# voting_machine.net
KiCad netlist of a schematic drawn in Altium Designer
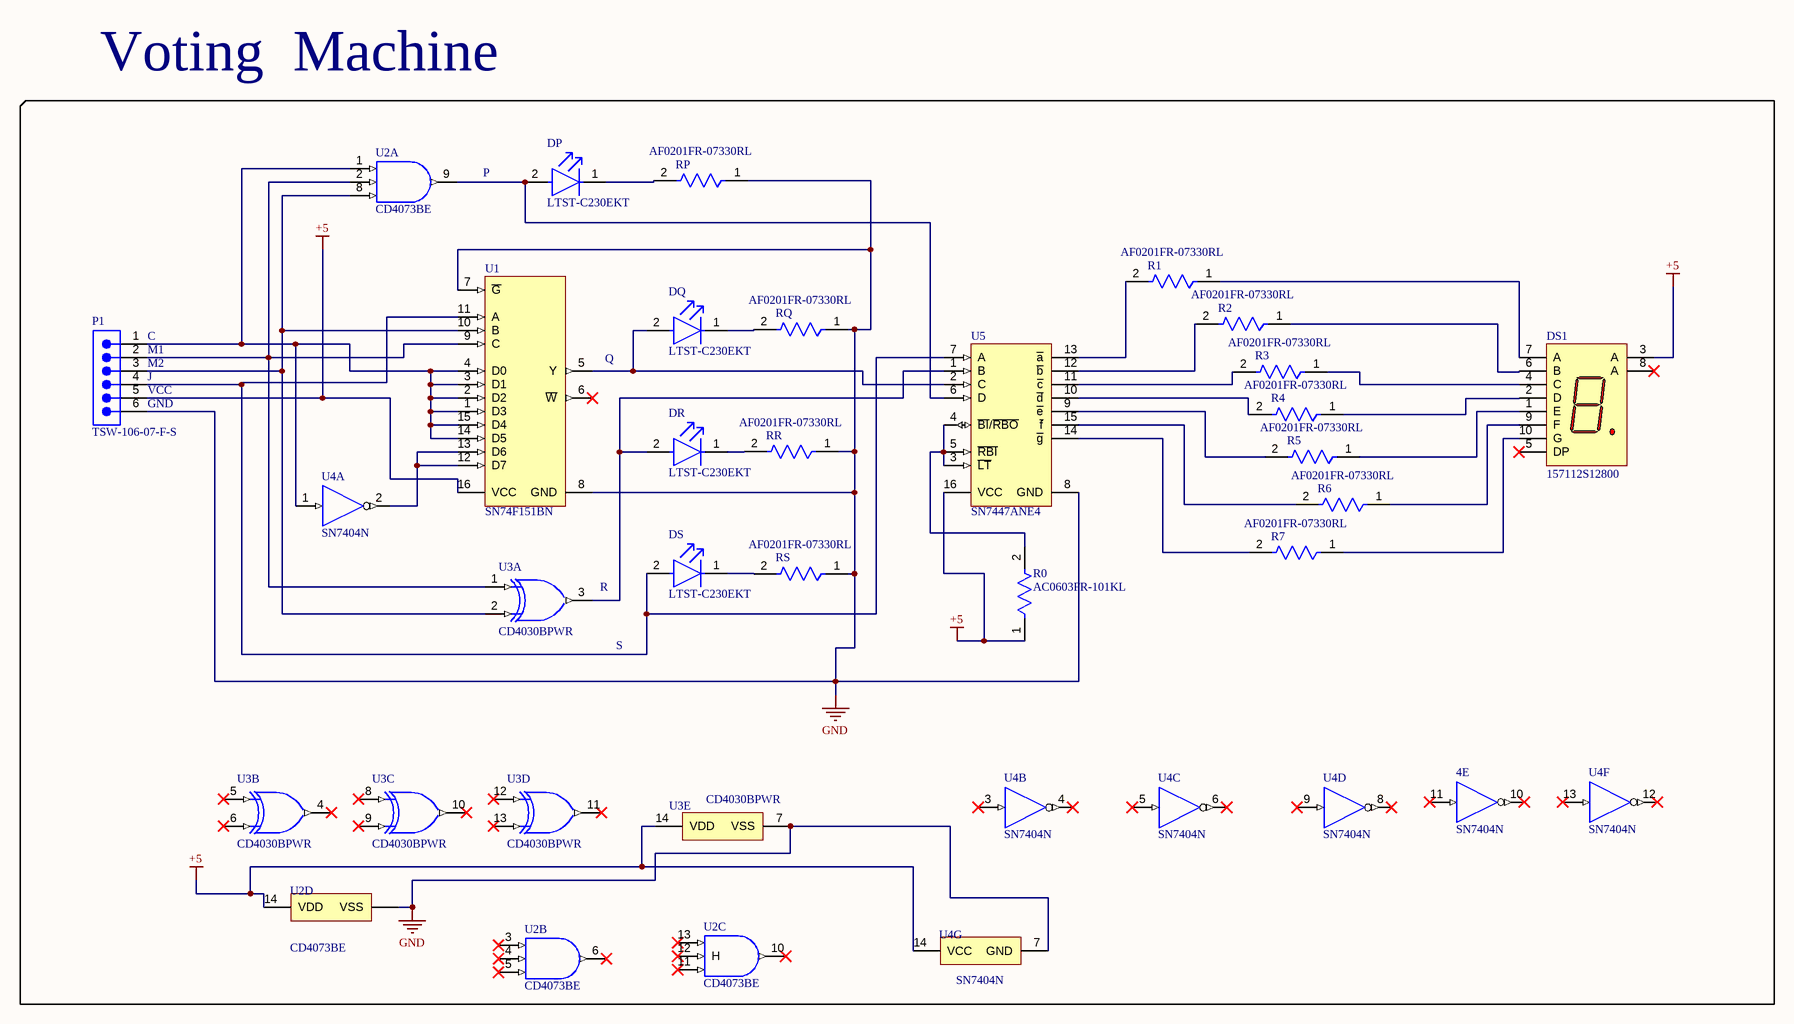
[diagram p0: voting machine.SchDoc]

(export (version "E")
  (design (tool "Eeschema 10.0.6"))
  (components
    (comp (ref "4")
      (value "SN7404N")
      (footprint "N0014A")
      (description "Hex inverters, N0014A, TUBE")
      (fields (field (name "GENERIC PART NUMBER") "SN7404") (field (name "MANUFACTURER") "Texas Instruments"))
      (libsource (lib "Altium Content Vault") (part "TI-CD_SNX4XXXXXX4X_19A-14"))
    )
    (comp (ref "DP")
      (value "LTST-C230EKT")
      (footprint "FP-LTST-C230EKT-MFG")
      (description "LED RED CLEAR CHIP SMD")
      (libsource (lib "Altium Content Vault") (part "8706943c75ba83719d021d2fdc84c58"))
    )
    (comp (ref "DQ")
      (value "LTST-C230EKT")
      (footprint "FP-LTST-C230EKT-MFG")
      (description "LED RED CLEAR CHIP SMD")
      (libsource (lib "Altium Content Vault") (part "8706943c75ba83719d021d2fdc84c58"))
    )
    (comp (ref "DR")
      (value "LTST-C230EKT")
      (footprint "FP-LTST-C230EKT-MFG")
      (description "LED RED CLEAR CHIP SMD")
      (libsource (lib "Altium Content Vault") (part "8706943c75ba83719d021d2fdc84c58"))
    )
    (comp (ref "DS")
      (value "LTST-C230EKT")
      (footprint "FP-LTST-C230EKT-MFG")
      (description "LED RED CLEAR CHIP SMD")
      (libsource (lib "Altium Content Vault") (part "8706943c75ba83719d021d2fdc84c58"))
    )
    (comp (ref "DS1")
      (value "157112S12800")
      (footprint "WL-S7DS_L12W7.3H3.75")
      (description "7-Seg Display, Comm Anode, Super Red Rohs Compliant: Yes")
      (libsource (lib "Altium Content Vault") (part "7 Segments_Red_CA_type 1"))
    )
    (comp (ref "P1")
      (value "TSW-106-07-F-S")
      (footprint "SMTC-TSW-106-07-X-S")
      (description "0.025\" SQ Post Header, Through-hole, Vertical, -55 to 125 degC, 2.54 mm Pitch, 6-Pin, Male, RoHS")
      (fields (field (name "MANUFACTURER") "Samtec"))
      (libsource (lib "Altium Content Vault") (part "SMTC-TSW-106-X-X-S-X"))
    )
    (comp (ref "R0")
      (value "AC0603FR-101KL")
      (footprint "FP-AC0603-IPC_C")
      (description "RES 1kΩ 1.00% 0.1W 0603")
      (fields (field (name "TOLERANCE") "1%"))
      (libsource (lib "Altium Content Vault") (part "1029c3af85768c4190bb7ad29bc67b5"))
    )
    (comp (ref "R1")
      (value "AF0201FR-07330RL")
      (footprint "FP-AF0201-MFG")
      (description "Anti-Sulfurated Chip Resistors Automotive Grade 330Ω 1% 200ppm/°C 0201")
      (fields (field (name "TOLERANCE") "1%"))
      (libsource (lib "Altium Content Vault") (part "1029c3af85768c4190bb7ad29bc67b5"))
    )
    (comp (ref "R2")
      (value "AF0201FR-07330RL")
      (footprint "FP-AF0201-MFG")
      (description "Anti-Sulfurated Chip Resistors Automotive Grade 330Ω 1% 200ppm/°C 0201")
      (fields (field (name "TOLERANCE") "1%"))
      (libsource (lib "Altium Content Vault") (part "1029c3af85768c4190bb7ad29bc67b5"))
    )
    (comp (ref "R3")
      (value "AF0201FR-07330RL")
      (footprint "FP-AF0201-MFG")
      (description "Anti-Sulfurated Chip Resistors Automotive Grade 330Ω 1% 200ppm/°C 0201")
      (fields (field (name "TOLERANCE") "1%"))
      (libsource (lib "Altium Content Vault") (part "1029c3af85768c4190bb7ad29bc67b5"))
    )
    (comp (ref "R4")
      (value "AF0201FR-07330RL")
      (footprint "FP-AF0201-MFG")
      (description "Anti-Sulfurated Chip Resistors Automotive Grade 330Ω 1% 200ppm/°C 0201")
      (fields (field (name "TOLERANCE") "1%"))
      (libsource (lib "Altium Content Vault") (part "1029c3af85768c4190bb7ad29bc67b5"))
    )
    (comp (ref "R5")
      (value "AF0201FR-07330RL")
      (footprint "FP-AF0201-MFG")
      (description "Anti-Sulfurated Chip Resistors Automotive Grade 330Ω 1% 200ppm/°C 0201")
      (fields (field (name "TOLERANCE") "1%"))
      (libsource (lib "Altium Content Vault") (part "1029c3af85768c4190bb7ad29bc67b5"))
    )
    (comp (ref "R6")
      (value "AF0201FR-07330RL")
      (footprint "FP-AF0201-MFG")
      (description "Anti-Sulfurated Chip Resistors Automotive Grade 330Ω 1% 200ppm/°C 0201")
      (fields (field (name "TOLERANCE") "1%"))
      (libsource (lib "Altium Content Vault") (part "1029c3af85768c4190bb7ad29bc67b5"))
    )
    (comp (ref "R7")
      (value "AF0201FR-07330RL")
      (footprint "FP-AF0201-MFG")
      (description "Anti-Sulfurated Chip Resistors Automotive Grade 330Ω 1% 200ppm/°C 0201")
      (fields (field (name "TOLERANCE") "1%"))
      (libsource (lib "Altium Content Vault") (part "1029c3af85768c4190bb7ad29bc67b5"))
    )
    (comp (ref "RP")
      (value "AF0201FR-07330RL")
      (footprint "FP-AF0201-MFG")
      (description "Anti-Sulfurated Chip Resistors Automotive Grade 330Ω 1% 200ppm/°C 0201")
      (fields (field (name "TOLERANCE") "1%"))
      (libsource (lib "Altium Content Vault") (part "1029c3af85768c4190bb7ad29bc67b5"))
    )
    (comp (ref "RQ")
      (value "AF0201FR-07330RL")
      (footprint "FP-AF0201-MFG")
      (description "Anti-Sulfurated Chip Resistors Automotive Grade 330Ω 1% 200ppm/°C 0201")
      (fields (field (name "TOLERANCE") "1%"))
      (libsource (lib "Altium Content Vault") (part "1029c3af85768c4190bb7ad29bc67b5"))
    )
    (comp (ref "RR")
      (value "AF0201FR-07330RL")
      (footprint "FP-AF0201-MFG")
      (description "Anti-Sulfurated Chip Resistors Automotive Grade 330Ω 1% 200ppm/°C 0201")
      (fields (field (name "TOLERANCE") "1%"))
      (libsource (lib "Altium Content Vault") (part "1029c3af85768c4190bb7ad29bc67b5"))
    )
    (comp (ref "RS")
      (value "AF0201FR-07330RL")
      (footprint "FP-AF0201-MFG")
      (description "Anti-Sulfurated Chip Resistors Automotive Grade 330Ω 1% 200ppm/°C 0201")
      (fields (field (name "TOLERANCE") "1%"))
      (libsource (lib "Altium Content Vault") (part "1029c3af85768c4190bb7ad29bc67b5"))
    )
    (comp (ref "U1")
      (value "SN74F151BN")
      (footprint "N0016A")
      (description "8-Line To 1-Line Data Selector/Multiplexer, N0016A, TUBE")
      (fields
        (field (name "MANUFACTURER") "Texas Instruments")
        (field (name "GENERIC PART NUMBER") "SN74F151B")
      )
      (libsource (lib "Altium Content Vault") (part "TI-SNX4XXX151-16"))
    )
    (comp (ref "U2")
      (value "CD4073BE")
      (footprint "N0014A")
      (description "CMOS Triple 3-Input AND Gate, N0014A, TUBE")
      (fields
        (field (name "MANUFACTURER") "Texas Instruments")
        (field (name "GENERIC PART NUMBER") "CD4073B")
      )
      (libsource (lib "Altium Content Vault") (part "TI-CD4073B-14"))
    )
    (comp (ref "U3")
      (value "CD4030BPWR")
      (footprint "PW0014A_M")
      (description "CMOS Quad Exclusive-OR Gate, PW0014A, LARGE T&R")
      (fields
        (field (name "MANUFACTURER") "Texas Instruments")
        (field (name "GENERIC PART NUMBER") "CD4030B")
      )
      (libsource (lib "Altium Content Vault") (part "TI-XOR-4-2IN-14_A"))
    )
    (comp (ref "U4")
      (value "SN7404N")
      (footprint "N0014A")
      (description "Hex inverters, N0014A, TUBE")
      (fields (field (name "GENERIC PART NUMBER") "SN7404") (field (name "MANUFACTURER") "Texas Instruments"))
      (libsource (lib "Altium Content Vault") (part "TI-CD_SNX4XXXXXX4X_19A-14"))
    )
    (comp (ref "U5")
      (value "SN7447ANE4")
      (footprint "TI-N16")
      (description "BCD-to-7-Segment Decoder / Driver, 4.75 to 5.25 V, 0 to 70 degC, 16-pin DIP (N16), Pb-Free (RoHS)")
      (fields (field (name "MANUFACTURER") "Texas Instruments"))
      (libsource (lib "Altium Content Vault") (part "TI-SNX4XX247-16"))
    )
  )
  (nets
    (net (code "1") (name "+5") (class "Default")
      (node (ref "DS1") (pin "3") (pinfunction "A_3") (pintype "passive"))
      (node (ref "P1") (pin "5") (pinfunction "5_5") (pintype "passive"))
      (node (ref "R0") (pin "1") (pinfunction "1_1") (pintype "passive"))
      (node (ref "U1") (pin "16") (pinfunction "VCC_16") (pintype "power_in"))
      (node (ref "U2") (pin "14") (pinfunction "VDD_14") (pintype "power_in"))
      (node (ref "U3") (pin "14") (pinfunction "VDD_14") (pintype "power_in"))
      (node (ref "U4") (pin "14") (pinfunction "VCC_14") (pintype "power_in"))
      (node (ref "U5") (pin "16") (pinfunction "VCC_16") (pintype "power_in"))
    )
    (net (code "2") (name "GND") (class "Default")
      (node (ref "P1") (pin "6") (pinfunction "6_6") (pintype "passive"))
      (node (ref "RP") (pin "1") (pinfunction "1_1") (pintype "passive"))
      (node (ref "RQ") (pin "1") (pinfunction "1_1") (pintype "passive"))
      (node (ref "RR") (pin "1") (pinfunction "1_1") (pintype "passive"))
      (node (ref "RS") (pin "1") (pinfunction "1_1") (pintype "passive"))
      (node (ref "U1") (pin "7") (pinfunction "~{G}_7") (pintype "input"))
      (node (ref "U1") (pin "8") (pinfunction "GND_8") (pintype "power_in"))
      (node (ref "U2") (pin "7") (pinfunction "VSS_7") (pintype "power_in"))
      (node (ref "U3") (pin "7") (pinfunction "VSS_7") (pintype "power_in"))
      (node (ref "U4") (pin "7") (pinfunction "GND_7") (pintype "power_in"))
      (node (ref "U5") (pin "8") (pinfunction "GND_8") (pintype "power_in"))
    )
    (net (code "3") (name "Net-(DP-A)") (class "Default")
      (node (ref "DP") (pin "2") (pinfunction "A_2") (pintype "passive"))
      (node (ref "U2") (pin "9") (pinfunction "J_9") (pintype "output"))
      (node (ref "U5") (pin "6") (pinfunction "D_6") (pintype "input"))
    )
    (net (code "4") (name "Net-(DP-C)") (class "Default")
      (node (ref "DP") (pin "1") (pinfunction "C_1") (pintype "passive"))
      (node (ref "RP") (pin "2") (pinfunction "2_2") (pintype "passive"))
    )
    (net (code "5") (name "Net-(DQ-A)") (class "Default")
      (node (ref "DQ") (pin "2") (pinfunction "A_2") (pintype "passive"))
      (node (ref "U1") (pin "5") (pinfunction "Y_5") (pintype "output"))
      (node (ref "U5") (pin "2") (pinfunction "C_2") (pintype "input"))
    )
    (net (code "6") (name "Net-(DQ-C)") (class "Default")
      (node (ref "DQ") (pin "1") (pinfunction "C_1") (pintype "passive"))
      (node (ref "RQ") (pin "2") (pinfunction "2_2") (pintype "passive"))
    )
    (net (code "7") (name "Net-(DR-A)") (class "Default")
      (node (ref "DR") (pin "2") (pinfunction "A_2") (pintype "passive"))
      (node (ref "U3") (pin "3") (pinfunction "J_3") (pintype "output"))
      (node (ref "U5") (pin "1") (pinfunction "B_1") (pintype "input"))
    )
    (net (code "8") (name "Net-(DR-C)") (class "Default")
      (node (ref "DR") (pin "1") (pinfunction "C_1") (pintype "passive"))
      (node (ref "RR") (pin "2") (pinfunction "2_2") (pintype "passive"))
    )
    (net (code "9") (name "Net-(DS-A)") (class "Default")
      (node (ref "DS") (pin "2") (pinfunction "A_2") (pintype "passive"))
      (node (ref "P1") (pin "4") (pinfunction "4_4") (pintype "passive"))
      (node (ref "U1") (pin "11") (pinfunction "A_11") (pintype "input"))
      (node (ref "U5") (pin "7") (pinfunction "A_7") (pintype "input"))
    )
    (net (code "10") (name "Net-(DS-C)") (class "Default")
      (node (ref "DS") (pin "1") (pinfunction "C_1") (pintype "passive"))
      (node (ref "RS") (pin "2") (pinfunction "2_2") (pintype "passive"))
    )
    (net (code "11") (name "Net-(DS1-A-Pad7)") (class "Default")
      (node (ref "DS1") (pin "7") (pinfunction "A_7") (pintype "passive"))
      (node (ref "R1") (pin "1") (pinfunction "1_1") (pintype "passive"))
    )
    (net (code "12") (name "Net-(DS1-B)") (class "Default")
      (node (ref "DS1") (pin "6") (pinfunction "B_6") (pintype "passive"))
      (node (ref "R2") (pin "1") (pinfunction "1_1") (pintype "passive"))
    )
    (net (code "13") (name "Net-(DS1-C)") (class "Default")
      (node (ref "DS1") (pin "4") (pinfunction "C_4") (pintype "passive"))
      (node (ref "R3") (pin "1") (pinfunction "1_1") (pintype "passive"))
    )
    (net (code "14") (name "Net-(DS1-D)") (class "Default")
      (node (ref "DS1") (pin "2") (pinfunction "D_2") (pintype "passive"))
      (node (ref "R4") (pin "1") (pinfunction "1_1") (pintype "passive"))
    )
    (net (code "15") (name "Net-(DS1-E)") (class "Default")
      (node (ref "DS1") (pin "1") (pinfunction "E_1") (pintype "passive"))
      (node (ref "R5") (pin "1") (pinfunction "1_1") (pintype "passive"))
    )
    (net (code "16") (name "Net-(DS1-F)") (class "Default")
      (node (ref "DS1") (pin "9") (pinfunction "F_9") (pintype "passive"))
      (node (ref "R6") (pin "1") (pinfunction "1_1") (pintype "passive"))
    )
    (net (code "17") (name "Net-(DS1-G)") (class "Default")
      (node (ref "DS1") (pin "10") (pinfunction "G_10") (pintype "passive"))
      (node (ref "R7") (pin "1") (pinfunction "1_1") (pintype "passive"))
    )
    (net (code "18") (name "Net-(U1-B)") (class "Default")
      (node (ref "P1") (pin "3") (pinfunction "3_3") (pintype "passive"))
      (node (ref "U1") (pin "10") (pinfunction "B_10") (pintype "input"))
      (node (ref "U2") (pin "8") (pinfunction "C_8") (pintype "input"))
      (node (ref "U3") (pin "2") (pinfunction "B_2") (pintype "input"))
    )
    (net (code "19") (name "Net-(U1-C)") (class "Default")
      (node (ref "P1") (pin "2") (pinfunction "2_2") (pintype "passive"))
      (node (ref "U1") (pin "9") (pinfunction "C_9") (pintype "input"))
      (node (ref "U2") (pin "2") (pinfunction "B_2") (pintype "input"))
      (node (ref "U3") (pin "1") (pinfunction "A_1") (pintype "input"))
    )
    (net (code "20") (name "Net-(U1-D0)") (class "Default")
      (node (ref "P1") (pin "1") (pinfunction "1_1") (pintype "passive"))
      (node (ref "U1") (pin "1") (pinfunction "D3_1") (pintype "input"))
      (node (ref "U1") (pin "14") (pinfunction "D5_14") (pintype "input"))
      (node (ref "U1") (pin "15") (pinfunction "D4_15") (pintype "input"))
      (node (ref "U1") (pin "2") (pinfunction "D2_2") (pintype "input"))
      (node (ref "U1") (pin "3") (pinfunction "D1_3") (pintype "input"))
      (node (ref "U1") (pin "4") (pinfunction "D0_4") (pintype "input"))
      (node (ref "U2") (pin "1") (pinfunction "A_1") (pintype "input"))
      (node (ref "U4") (pin "1") (pinfunction "1A_1") (pintype "input"))
    )
    (net (code "21") (name "Net-(U1-D6)") (class "Default")
      (node (ref "U1") (pin "12") (pinfunction "D7_12") (pintype "input"))
      (node (ref "U1") (pin "13") (pinfunction "D6_13") (pintype "input"))
      (node (ref "U4") (pin "2") (pinfunction "~{1Y}_2") (pintype "output"))
    )
    (net (code "22") (name "Net-(U5-~{BI}{slash}~{RBO})") (class "Default")
      (node (ref "R0") (pin "2") (pinfunction "2_2") (pintype "passive"))
      (node (ref "U5") (pin "3") (pinfunction "~{LT}_3") (pintype "input"))
      (node (ref "U5") (pin "4") (pinfunction "~{BI}/~{RBO}_4") (pintype "bidirectional"))
      (node (ref "U5") (pin "5") (pinfunction "~{RBI}_5") (pintype "input"))
    )
    (net (code "23") (name "Net-(U5-~{a})") (class "Default")
      (node (ref "R1") (pin "2") (pinfunction "2_2") (pintype "passive"))
      (node (ref "U5") (pin "13") (pinfunction "~{a}_13") (pintype "open_collector"))
    )
    (net (code "24") (name "Net-(U5-~{b})") (class "Default")
      (node (ref "R2") (pin "2") (pinfunction "2_2") (pintype "passive"))
      (node (ref "U5") (pin "12") (pinfunction "~{b}_12") (pintype "open_collector"))
    )
    (net (code "25") (name "Net-(U5-~{c})") (class "Default")
      (node (ref "R3") (pin "2") (pinfunction "2_2") (pintype "passive"))
      (node (ref "U5") (pin "11") (pinfunction "~{c}_11") (pintype "open_collector"))
    )
    (net (code "26") (name "Net-(U5-~{d})") (class "Default")
      (node (ref "R4") (pin "2") (pinfunction "2_2") (pintype "passive"))
      (node (ref "U5") (pin "10") (pinfunction "~{d}_10") (pintype "open_collector"))
    )
    (net (code "27") (name "Net-(U5-~{e})") (class "Default")
      (node (ref "R5") (pin "2") (pinfunction "2_2") (pintype "passive"))
      (node (ref "U5") (pin "9") (pinfunction "~{e}_9") (pintype "open_collector"))
    )
    (net (code "28") (name "Net-(U5-~{f})") (class "Default")
      (node (ref "R6") (pin "2") (pinfunction "2_2") (pintype "passive"))
      (node (ref "U5") (pin "15") (pinfunction "~{f}_15") (pintype "open_collector"))
    )
    (net (code "29") (name "Net-(U5-~{g})") (class "Default")
      (node (ref "R7") (pin "2") (pinfunction "2_2") (pintype "passive"))
      (node (ref "U5") (pin "14") (pinfunction "~{g}_14") (pintype "open_collector"))
    )
    (net (code "30") (name "unconnected-(4E-5A-Pad11)") (class "Default")
      (node (ref "4") (pin "11") (pinfunction "5A_11") (pintype "input+no_connect"))
    )
    (net (code "31") (name "unconnected-(4E-~{5Y}-Pad10)") (class "Default")
      (node (ref "4") (pin "10") (pinfunction "~{5Y}_10") (pintype "output+no_connect"))
    )
    (net (code "32") (name "unconnected-(DS1-A-Pad8)") (class "Default")
      (node (ref "DS1") (pin "8") (pinfunction "A_8") (pintype "passive+no_connect"))
    )
    (net (code "33") (name "unconnected-(DS1-DP-Pad5)") (class "Default")
      (node (ref "DS1") (pin "5") (pinfunction "DP_5") (pintype "passive+no_connect"))
    )
    (net (code "34") (name "unconnected-(U1-~{W}-Pad6)") (class "Default")
      (node (ref "U1") (pin "6") (pinfunction "~{W}_6") (pintype "output+no_connect"))
    )
    (net (code "35") (name "unconnected-(U2B-D-Pad3)") (class "Default")
      (node (ref "U2") (pin "3") (pinfunction "D_3") (pintype "input+no_connect"))
    )
    (net (code "36") (name "unconnected-(U2B-E-Pad4)") (class "Default")
      (node (ref "U2") (pin "4") (pinfunction "E_4") (pintype "input+no_connect"))
    )
    (net (code "37") (name "unconnected-(U2B-F-Pad5)") (class "Default")
      (node (ref "U2") (pin "5") (pinfunction "F_5") (pintype "input+no_connect"))
    )
    (net (code "38") (name "unconnected-(U2B-K-Pad6)") (class "Default")
      (node (ref "U2") (pin "6") (pinfunction "K_6") (pintype "output+no_connect"))
    )
    (net (code "39") (name "unconnected-(U2C-G-Pad13)") (class "Default")
      (node (ref "U2") (pin "13") (pinfunction "G_13") (pintype "input+no_connect"))
    )
    (net (code "40") (name "unconnected-(U2C-H-Pad12)") (class "Default")
      (node (ref "U2") (pin "12") (pinfunction "H_12") (pintype "input+no_connect"))
    )
    (net (code "41") (name "unconnected-(U2C-I-Pad11)") (class "Default")
      (node (ref "U2") (pin "11") (pinfunction "I_11") (pintype "input+no_connect"))
    )
    (net (code "42") (name "unconnected-(U2C-L-Pad10)") (class "Default")
      (node (ref "U2") (pin "10") (pinfunction "L_10") (pintype "output+no_connect"))
    )
    (net (code "43") (name "unconnected-(U3B-C-Pad5)") (class "Default")
      (node (ref "U3") (pin "5") (pinfunction "C_5") (pintype "input+no_connect"))
    )
    (net (code "44") (name "unconnected-(U3B-D-Pad6)") (class "Default")
      (node (ref "U3") (pin "6") (pinfunction "D_6") (pintype "input+no_connect"))
    )
    (net (code "45") (name "unconnected-(U3B-K-Pad4)") (class "Default")
      (node (ref "U3") (pin "4") (pinfunction "K_4") (pintype "output+no_connect"))
    )
    (net (code "46") (name "unconnected-(U3C-E-Pad8)") (class "Default")
      (node (ref "U3") (pin "8") (pinfunction "E_8") (pintype "input+no_connect"))
    )
    (net (code "47") (name "unconnected-(U3C-F-Pad9)") (class "Default")
      (node (ref "U3") (pin "9") (pinfunction "F_9") (pintype "input+no_connect"))
    )
    (net (code "48") (name "unconnected-(U3C-L-Pad10)") (class "Default")
      (node (ref "U3") (pin "10") (pinfunction "L_10") (pintype "output+no_connect"))
    )
    (net (code "49") (name "unconnected-(U3D-G-Pad12)") (class "Default")
      (node (ref "U3") (pin "12") (pinfunction "G_12") (pintype "input+no_connect"))
    )
    (net (code "50") (name "unconnected-(U3D-H-Pad13)") (class "Default")
      (node (ref "U3") (pin "13") (pinfunction "H_13") (pintype "input+no_connect"))
    )
    (net (code "51") (name "unconnected-(U3D-M-Pad11)") (class "Default")
      (node (ref "U3") (pin "11") (pinfunction "M_11") (pintype "output+no_connect"))
    )
    (net (code "52") (name "unconnected-(U4B-2A-Pad3)") (class "Default")
      (node (ref "U4") (pin "3") (pinfunction "2A_3") (pintype "input+no_connect"))
    )
    (net (code "53") (name "unconnected-(U4B-~{2Y}-Pad4)") (class "Default")
      (node (ref "U4") (pin "4") (pinfunction "~{2Y}_4") (pintype "output+no_connect"))
    )
    (net (code "54") (name "unconnected-(U4C-3A-Pad5)") (class "Default")
      (node (ref "U4") (pin "5") (pinfunction "3A_5") (pintype "input+no_connect"))
    )
    (net (code "55") (name "unconnected-(U4C-~{3Y}-Pad6)") (class "Default")
      (node (ref "U4") (pin "6") (pinfunction "~{3Y}_6") (pintype "output+no_connect"))
    )
    (net (code "56") (name "unconnected-(U4D-4A-Pad9)") (class "Default")
      (node (ref "U4") (pin "9") (pinfunction "4A_9") (pintype "input+no_connect"))
    )
    (net (code "57") (name "unconnected-(U4D-~{4Y}-Pad8)") (class "Default")
      (node (ref "U4") (pin "8") (pinfunction "~{4Y}_8") (pintype "output+no_connect"))
    )
    (net (code "58") (name "unconnected-(U4F-6A-Pad13)") (class "Default")
      (node (ref "U4") (pin "13") (pinfunction "6A_13") (pintype "input+no_connect"))
    )
    (net (code "59") (name "unconnected-(U4F-~{6Y}-Pad12)") (class "Default")
      (node (ref "U4") (pin "12") (pinfunction "~{6Y}_12") (pintype "output+no_connect"))
    )
  )
)
